# openSX70_MEROEC_V7-9C_20200625-TCS3200.net
KiCad netlist of a schematic drawn in EAGLE
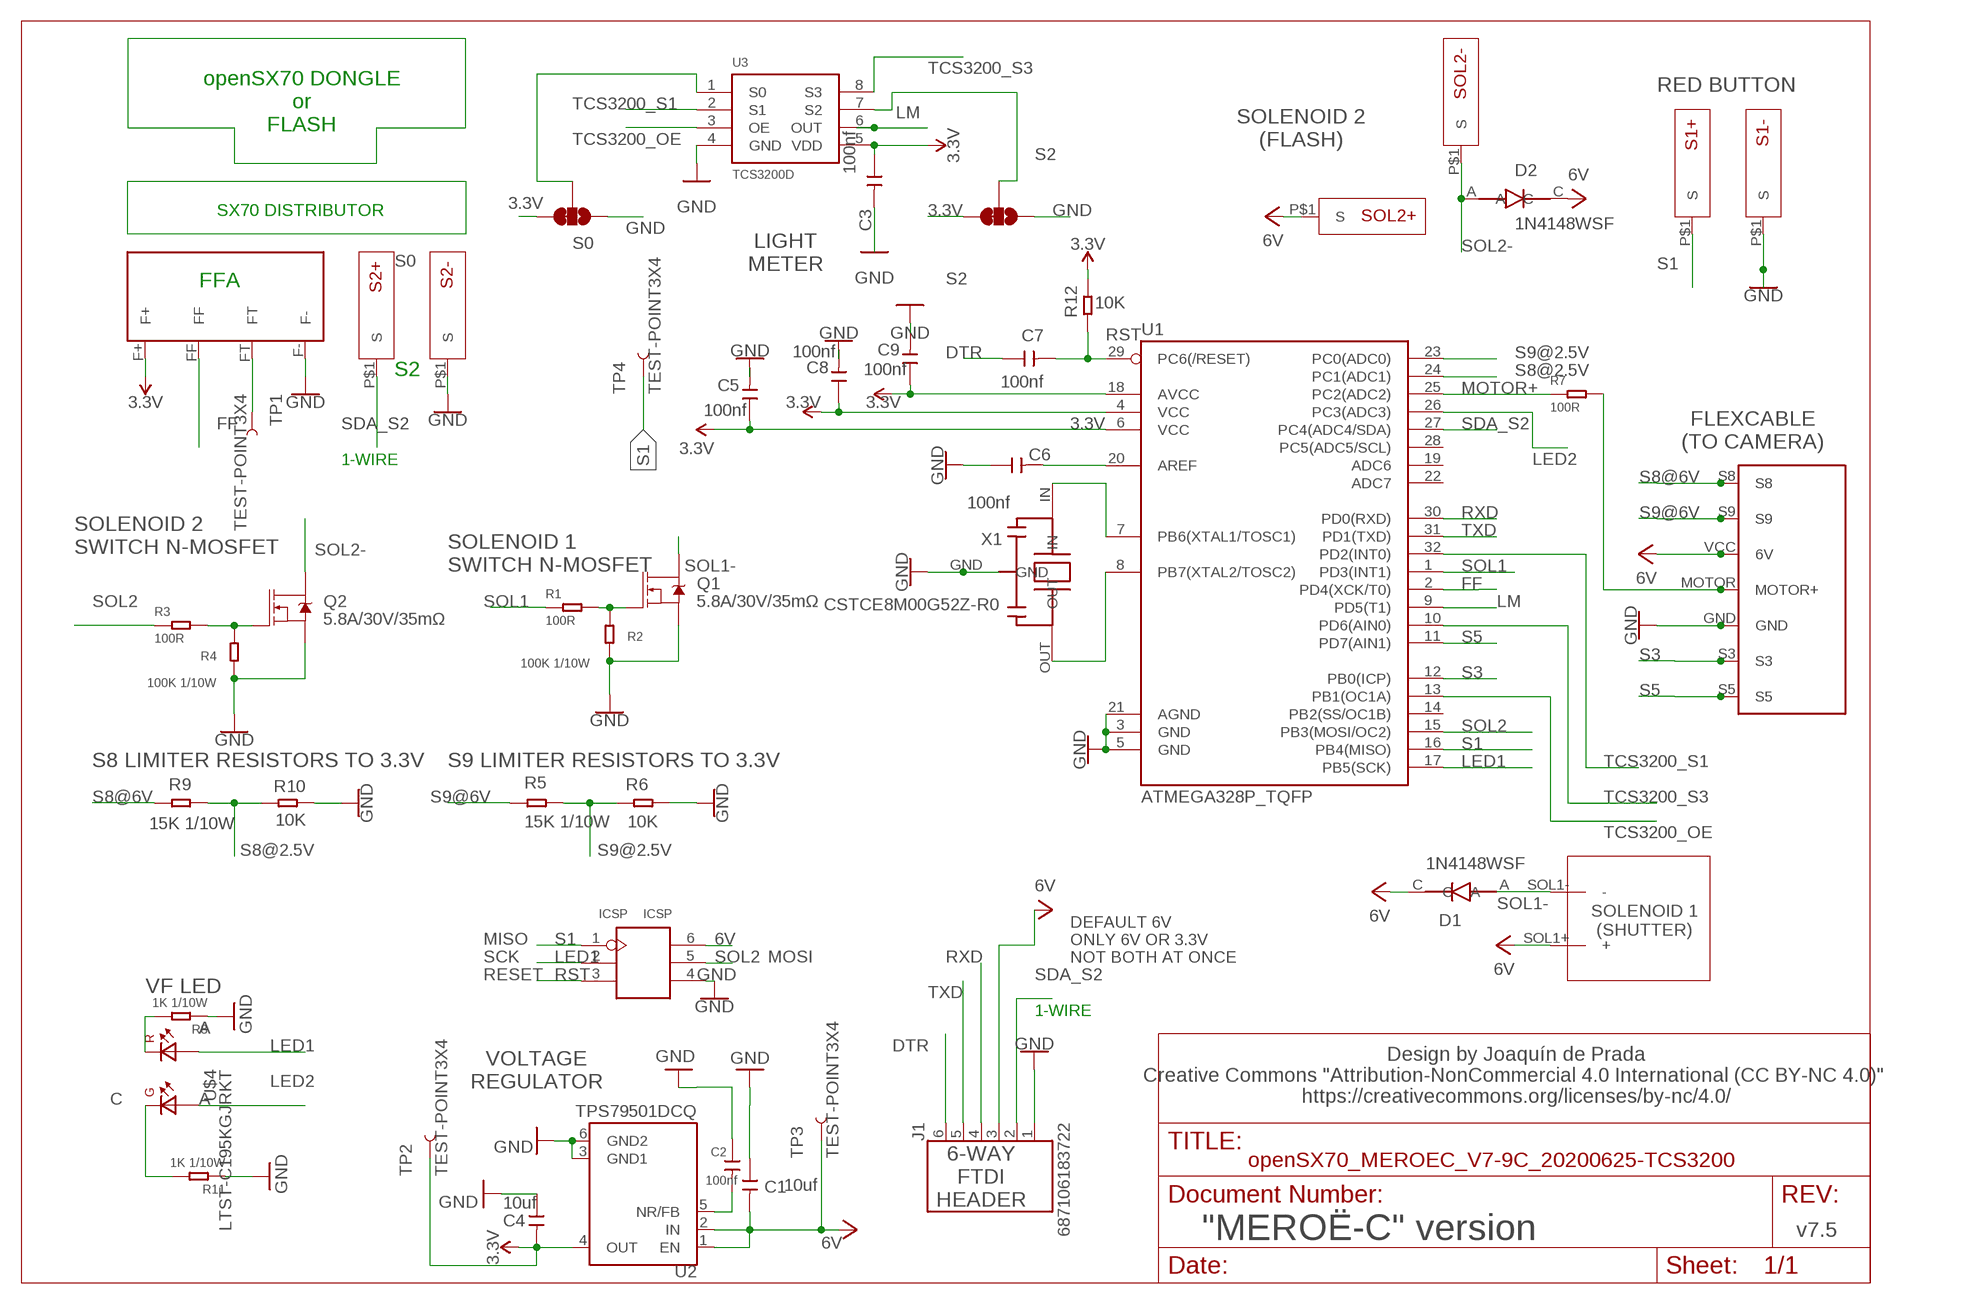
[diagram p0: schematic, sheet 1]

(export (version "E")
  (design (tool "Eeschema 10.0.6"))
  (components
    (comp (ref "C1")
      (value "10uf")
      (footprint "eagle-import:C0603")
      (fields (field (name "MPN") "CC0603KRX5R6BB106"))
      (libsource (lib "eagle-import") (part "CERAMIC-10UF-10V-10%-X5R(0603)"))
    )
    (comp (ref "C2")
      (value "100nf")
      (footprint "eagle-import:C0603")
      (fields (field (name "MPN") "CC0603KRX7R9BB104"))
      (libsource (lib "eagle-import") (part "CERAMIC-100NF-50V-10%-X7R(0603)"))
    )
    (comp (ref "C3")
      (value "100nf")
      (footprint "eagle-import:C0603")
      (fields (field (name "MPN") "CC0603KRX7R9BB104"))
      (libsource (lib "eagle-import") (part "CERAMIC-100NF-50V-10%-X7R(0603)"))
    )
    (comp (ref "C4")
      (value "10uf")
      (footprint "eagle-import:C0603")
      (fields (field (name "MPN") "CC0603KRX5R6BB106"))
      (libsource (lib "eagle-import") (part "CERAMIC-10UF-10V-10%-X5R(0603)"))
    )
    (comp (ref "C5")
      (value "100nf")
      (footprint "eagle-import:C0603")
      (fields (field (name "MPN") "CC0603KRX7R9BB104"))
      (libsource (lib "eagle-import") (part "CERAMIC-100NF-50V-10%-X7R(0603)"))
    )
    (comp (ref "C6")
      (value "100nf")
      (footprint "eagle-import:C0603")
      (fields (field (name "MPN") "CC0603KRX7R9BB104"))
      (libsource (lib "eagle-import") (part "CERAMIC-100NF-50V-10%-X7R(0603)"))
    )
    (comp (ref "C7")
      (value "100nf")
      (footprint "eagle-import:C0603")
      (fields (field (name "MPN") "CC0603KRX7R9BB104"))
      (libsource (lib "eagle-import") (part "CERAMIC-100NF-50V-10%-X7R(0603)"))
    )
    (comp (ref "C8")
      (value "100nf")
      (footprint "eagle-import:C0603")
      (fields (field (name "MPN") "CC0603KRX7R9BB104"))
      (libsource (lib "eagle-import") (part "CERAMIC-100NF-50V-10%-X7R(0603)"))
    )
    (comp (ref "C9")
      (value "100nf")
      (footprint "eagle-import:C0603")
      (fields (field (name "MPN") "CC0603KRX7R9BB104"))
      (libsource (lib "eagle-import") (part "CERAMIC-100NF-50V-10%-X7R(0603)"))
    )
    (comp (ref "D1")
      (value "1N4148WSF")
      (footprint "eagle-import:SODFL2512X100N")
      (fields (field (name "MANUFACTURER") "Fairchild Semiconductor"))
      (libsource (lib "eagle-import") (part "1N4148WS"))
    )
    (comp (ref "D2")
      (value "1N4148WSF")
      (footprint "eagle-import:SODFL2512X100N")
      (fields (field (name "MANUFACTURER") "Fairchild Semiconductor"))
      (libsource (lib "eagle-import") (part "1N4148WS"))
    )
    (comp (ref "ICSP")
      (value "ICSP")
      (footprint "eagle-import:H2X3-2.54")
      (libsource (lib "eagle-import") (part "ICSP"))
    )
    (comp (ref "J1")
      (value "687106183722")
      (footprint "eagle-import:687106183722")
      (fields (field (name "MF") "Wurth Electronics"))
      (libsource (lib "eagle-import") (part "687106183722"))
    )
    (comp (ref "Q1")
      (value "5.8A/30V/35mΩ")
      (footprint "eagle-import:SOT23-3")
      (libsource (lib "eagle-import") (part "MOSFET-NCH-AO3404A"))
    )
    (comp (ref "Q2")
      (value "5.8A/30V/35mΩ")
      (footprint "eagle-import:SOT23-3")
      (libsource (lib "eagle-import") (part "MOSFET-NCH-AO3404A"))
    )
    (comp (ref "R1")
      (value "100R")
      (footprint "eagle-import:R0603")
      (fields (field (name "MPN") "RC0603JR-07100RL"))
      (libsource (lib "eagle-import") (part "SMD-RES-100R-5%-1/10W(0603)"))
    )
    (comp (ref "R2")
      (value "100K 1/10W")
      (footprint "eagle-import:R0603")
      (fields (field (name "MPN") "RC0603JR-07100KL"))
      (libsource (lib "eagle-import") (part "SMD-RES-100K-5%-1/10W(0603)"))
    )
    (comp (ref "R3")
      (value "100R")
      (footprint "eagle-import:R0603")
      (fields (field (name "MPN") "RC0603JR-07100RL"))
      (libsource (lib "eagle-import") (part "SMD-RES-100R-5%-1/10W(0603)"))
    )
    (comp (ref "R4")
      (value "100K 1/10W")
      (footprint "eagle-import:R0603")
      (fields (field (name "MPN") "RC0603JR-07100KL"))
      (libsource (lib "eagle-import") (part "SMD-RES-100K-5%-1/10W(0603)"))
    )
    (comp (ref "R5")
      (value "15K 1/10W")
      (footprint "eagle-import:R0603")
      (fields (field (name "MPN") "RC0603FR-0715KL"))
      (libsource (lib "eagle-import") (part "SMD-RES-15K-1%-1/10W(0603)"))
    )
    (comp (ref "R6")
      (value "10K")
      (footprint "eagle-import:R0603")
      (fields (field (name "MPN") "RC0603FR-0710KL"))
      (libsource (lib "eagle-import") (part "SMD-RES-10K-1%-1/10W(0603)"))
    )
    (comp (ref "R7")
      (value "100R")
      (footprint "eagle-import:R0603")
      (fields (field (name "MPN") "RC0603JR-07100RL"))
      (libsource (lib "eagle-import") (part "SMD-RES-100R-5%-1/10W(0603)"))
    )
    (comp (ref "R8")
      (value "1K 1/10W")
      (footprint "eagle-import:R0603")
      (fields (field (name "MPN") "RC0603JR-071KL"))
      (libsource (lib "eagle-import") (part "SMD-RES-1K-5%-1/10W(0603)"))
    )
    (comp (ref "R9")
      (value "15K 1/10W")
      (footprint "eagle-import:R0603")
      (fields (field (name "MPN") "RC0603FR-0715KL"))
      (libsource (lib "eagle-import") (part "SMD-RES-15K-1%-1/10W(0603)"))
    )
    (comp (ref "R10")
      (value "10K")
      (footprint "eagle-import:R0603")
      (fields (field (name "MPN") "RC0603FR-0710KL"))
      (libsource (lib "eagle-import") (part "SMD-RES-10K-1%-1/10W(0603)"))
    )
    (comp (ref "R11")
      (value "1K 1/10W")
      (footprint "eagle-import:R0603")
      (fields (field (name "MPN") "RC0603JR-071KL"))
      (libsource (lib "eagle-import") (part "SMD-RES-1K-5%-1/10W(0603)"))
    )
    (comp (ref "R12")
      (value "10K")
      (footprint "eagle-import:R0603")
      (fields (field (name "MPN") "RC0603FR-0710KL"))
      (libsource (lib "eagle-import") (part "SMD-RES-10K-1%-1/10W(0603)"))
    )
    (comp (ref "S0")
      (value "S0")
      (footprint "eagle-import:SMT-JUMPER_3_1-NC_TRACE_SILK")
      (libsource (lib "eagle-import") (part "JUMPER-SMT_3_1-NC_TRACE_SILK"))
    )
    (comp (ref "S1+")
      (value "SX70-S-PAD-NEW")
      (footprint "eagle-import:SX70-S-PAD2")
      (libsource (lib "eagle-import") (part "SX70-S-PAD-NEW"))
    )
    (comp (ref "S1-")
      (value "SX70-S-PAD-NEW")
      (footprint "eagle-import:SX70-S-PAD2")
      (libsource (lib "eagle-import") (part "SX70-S-PAD-NEW"))
    )
    (comp (ref "S2")
      (value "S2")
      (footprint "eagle-import:SMT-JUMPER_3_1-NC_TRACE_SILK")
      (libsource (lib "eagle-import") (part "JUMPER-SMT_3_1-NC_TRACE_SILK"))
    )
    (comp (ref "S2+")
      (value "SX70-S-PAD-NEW")
      (footprint "eagle-import:SX70-S-PAD2")
      (libsource (lib "eagle-import") (part "SX70-S-PAD-NEW"))
    )
    (comp (ref "S2-")
      (value "SX70-S-PAD-NEW")
      (footprint "eagle-import:SX70-S-PAD2")
      (libsource (lib "eagle-import") (part "SX70-S-PAD-NEW"))
    )
    (comp (ref "SOL1")
      (value "SX70-SOLENOID1-2PADS")
      (footprint "eagle-import:SX70-SOLENOID1-2")
      (libsource (lib "eagle-import") (part "SX70-SOLENOID1-2PADS"))
    )
    (comp (ref "SOL2+")
      (value "SX70-S-PAD-NEW")
      (footprint "eagle-import:SX70-S-PAD2")
      (libsource (lib "eagle-import") (part "SX70-S-PAD-NEW"))
    )
    (comp (ref "SOL2-")
      (value "SX70-S-PAD-NEW")
      (footprint "eagle-import:SX70-S-PAD2")
      (libsource (lib "eagle-import") (part "SX70-S-PAD-NEW"))
    )
    (comp (ref "TP1")
      (value "TEST-POINT3X4")
      (footprint "eagle-import:PAD.03X.04")
      (libsource (lib "eagle-import") (part "TEST-POINT3X4"))
    )
    (comp (ref "TP2")
      (value "TEST-POINT3X4")
      (footprint "eagle-import:PAD.03X.04")
      (libsource (lib "eagle-import") (part "TEST-POINT3X4"))
    )
    (comp (ref "TP3")
      (value "TEST-POINT3X4")
      (footprint "eagle-import:PAD.03X.04")
      (libsource (lib "eagle-import") (part "TEST-POINT3X4"))
    )
    (comp (ref "TP4")
      (value "TEST-POINT3X4")
      (footprint "eagle-import:PAD.03X.04")
      (libsource (lib "eagle-import") (part "TEST-POINT3X4"))
    )
    (comp (ref "U$1")
      (value "SX70-7-PAD")
      (footprint "eagle-import:SX70-7-PAD-PROPER")
      (libsource (lib "eagle-import") (part "SX70-7-PAD"))
    )
    (comp (ref "U$2")
      (value "FFA")
      (footprint "eagle-import:FFA-PAD-PACKAGE")
      (libsource (lib "eagle-import") (part "SX70-FFA-PAD"))
    )
    (comp (ref "U$4")
      (value "LTST-C195KGJRKT")
      (footprint "eagle-import:LTST-BILED-15X16")
      (fields (field (name "MF") "Lite-On Inc."))
      (libsource (lib "eagle-import") (part "LTST-C195KGJRKT"))
    )
    (comp (ref "U1")
      (value "ATMEGA328P_TQFP")
      (footprint "eagle-import:TQFP32-08")
      (libsource (lib "eagle-import") (part "ATMEGA328P_TQFP"))
    )
    (comp (ref "U2")
      (value "TPS79501DCQ")
      (footprint "eagle-import:SOT127P706X180-6N")
      (fields (field (name "MF") "Texas Instruments"))
      (libsource (lib "eagle-import") (part "TPS79501DCQ"))
    )
    (comp (ref "U3")
      (value "TCS3200D")
      (footprint "eagle-import:SOIC8")
      (fields (field (name "MF") "ams") (field (name "MP") "TCS3200D-TR"))
      (libsource (lib "eagle-import") (part "TCS3200D"))
    )
    (comp (ref "X1")
      (value "CSTCE8M00G52Z-R0")
      (footprint "eagle-import:CFP95P160X100-3N")
      (fields (field (name "MF") "Murata") (field (name "MP") "CSTCE16M0V53-R0"))
      (libsource (lib "eagle-import") (part "CSTCE16M0V53-R0"))
    )
  )
  (nets
    (net (code "1") (name "/DTR") (class "Default")
      (node (ref "C7") (pin "1") (pinfunction "1_1") (pintype "passive"))
      (node (ref "J1") (pin "6") (pinfunction "1_6") (pintype "passive"))
    )
    (net (code "2") (name "/FF") (class "Default")
      (node (ref "U$2") (pin "FF") (pinfunction "FF_FF") (pintype "bidirectional"))
      (node (ref "U1") (pin "2") (pinfunction "PD4(XCK/T0)_2") (pintype "bidirectional"))
    )
    (net (code "3") (name "/LED1") (class "Default")
      (node (ref "ICSP") (pin "2") (pinfunction "SCK_2") (pintype "bidirectional"))
      (node (ref "U$4") (pin "P$2") (pinfunction "A2_P$2") (pintype "passive"))
      (node (ref "U1") (pin "17") (pinfunction "PB5(SCK)_17") (pintype "bidirectional"))
    )
    (net (code "4") (name "/LED2") (class "Default")
      (node (ref "U$4") (pin "P$1") (pinfunction "A1_P$1") (pintype "passive"))
      (node (ref "U1") (pin "26") (pinfunction "PC3(ADC3)_26") (pintype "bidirectional"))
    )
    (net (code "5") (name "/LM") (class "Default")
      (node (ref "U1") (pin "9") (pinfunction "PD5(T1)_9") (pintype "bidirectional"))
      (node (ref "U3") (pin "6") (pinfunction "OUT_6") (pintype "bidirectional"))
    )
    (net (code "6") (name "/MOTOR+") (class "Default")
      (node (ref "R7") (pin "1") (pinfunction "1_1") (pintype "passive"))
      (node (ref "U1") (pin "25") (pinfunction "PC2(ADC2)_25") (pintype "bidirectional"))
    )
    (net (code "7") (name "/RST") (class "Default")
      (node (ref "C7") (pin "2") (pinfunction "2_2") (pintype "passive"))
      (node (ref "ICSP") (pin "3") (pinfunction "RST_3") (pintype "bidirectional"))
      (node (ref "R12") (pin "1") (pinfunction "1_1") (pintype "passive"))
      (node (ref "U1") (pin "29") (pinfunction "PC6(/RESET)_29") (pintype "bidirectional"))
    )
    (net (code "8") (name "/RXD") (class "Default")
      (node (ref "J1") (pin "4") (pinfunction "3_4") (pintype "passive"))
      (node (ref "U1") (pin "30") (pinfunction "PD0(RXD)_30") (pintype "bidirectional"))
    )
    (net (code "9") (name "/S3") (class "Default")
      (node (ref "U$1") (pin "S3") (pinfunction "S3_S3") (pintype "bidirectional"))
      (node (ref "U1") (pin "12") (pinfunction "PB0(ICP)_12") (pintype "bidirectional"))
    )
    (net (code "10") (name "/S5") (class "Default")
      (node (ref "U$1") (pin "S5") (pinfunction "S5_S5") (pintype "bidirectional"))
      (node (ref "U1") (pin "11") (pinfunction "PD7(AIN1)_11") (pintype "bidirectional"))
    )
    (net (code "11") (name "/S8@2.5V") (class "Default")
      (node (ref "R10") (pin "1") (pinfunction "1_1") (pintype "passive"))
      (node (ref "R9") (pin "2") (pinfunction "2_2") (pintype "passive"))
      (node (ref "U1") (pin "24") (pinfunction "PC1(ADC1)_24") (pintype "bidirectional"))
    )
    (net (code "12") (name "/S8@6V") (class "Default")
      (node (ref "R9") (pin "1") (pinfunction "1_1") (pintype "passive"))
      (node (ref "U$1") (pin "S8") (pinfunction "S8_S8") (pintype "bidirectional"))
    )
    (net (code "13") (name "/S9@2.5V") (class "Default")
      (node (ref "R5") (pin "2") (pinfunction "2_2") (pintype "passive"))
      (node (ref "R6") (pin "1") (pinfunction "1_1") (pintype "passive"))
      (node (ref "U1") (pin "23") (pinfunction "PC0(ADC0)_23") (pintype "bidirectional"))
    )
    (net (code "14") (name "/S9@6V") (class "Default")
      (node (ref "R5") (pin "1") (pinfunction "1_1") (pintype "passive"))
      (node (ref "U$1") (pin "S9") (pinfunction "S9_S9") (pintype "bidirectional"))
    )
    (net (code "15") (name "/SDA_S2") (class "Default")
      (node (ref "J1") (pin "2") (pinfunction "5_2") (pintype "passive"))
      (node (ref "S2+") (pin "P$1") (pinfunction "S_P$1") (pintype "bidirectional"))
      (node (ref "U1") (pin "27") (pinfunction "PC4(ADC4/SDA)_27") (pintype "bidirectional"))
    )
    (net (code "16") (name "/SOL1") (class "Default")
      (node (ref "R1") (pin "1") (pinfunction "1_1") (pintype "passive"))
      (node (ref "U1") (pin "1") (pinfunction "PD3(INT1)_1") (pintype "bidirectional"))
    )
    (net (code "17") (name "/SOL1-") (class "Default")
      (node (ref "D1") (pin "A") (pinfunction "A_A") (pintype "passive"))
      (node (ref "Q1") (pin "3") (pinfunction "D_3") (pintype "bidirectional"))
      (node (ref "SOL1") (pin "SOL1-") (pinfunction "-_SOL1-") (pintype "bidirectional"))
    )
    (net (code "18") (name "/SOL2") (class "Default")
      (node (ref "ICSP") (pin "5") (pinfunction "MOSI_5") (pintype "bidirectional"))
      (node (ref "R3") (pin "1") (pinfunction "1_1") (pintype "passive"))
      (node (ref "U1") (pin "15") (pinfunction "PB3(MOSI/OC2)_15") (pintype "bidirectional"))
    )
    (net (code "19") (name "/SOL2-") (class "Default")
      (node (ref "D2") (pin "A") (pinfunction "A_A") (pintype "passive"))
      (node (ref "Q2") (pin "3") (pinfunction "D_3") (pintype "bidirectional"))
      (node (ref "SOL2-") (pin "P$1") (pinfunction "S_P$1") (pintype "bidirectional"))
    )
    (net (code "20") (name "/TCS3200_OE") (class "Default")
      (node (ref "U1") (pin "13") (pinfunction "PB1(OC1A)_13") (pintype "bidirectional"))
      (node (ref "U3") (pin "3") (pinfunction "OE_3") (pintype "bidirectional"))
    )
    (net (code "21") (name "/TCS3200_S1") (class "Default")
      (node (ref "U1") (pin "32") (pinfunction "PD2(INT0)_32") (pintype "bidirectional"))
      (node (ref "U3") (pin "2") (pinfunction "S1_2") (pintype "bidirectional"))
    )
    (net (code "22") (name "/TCS3200_S3") (class "Default")
      (node (ref "U1") (pin "10") (pinfunction "PD6(AIN0)_10") (pintype "bidirectional"))
      (node (ref "U3") (pin "8") (pinfunction "S3_8") (pintype "bidirectional"))
    )
    (net (code "23") (name "/TXD") (class "Default")
      (node (ref "J1") (pin "5") (pinfunction "2_5") (pintype "passive"))
      (node (ref "U1") (pin "31") (pinfunction "PD1(TXD)_31") (pintype "bidirectional"))
    )
    (net (code "24") (name "3.3V") (class "Default")
      (node (ref "C3") (pin "1") (pinfunction "1_1") (pintype "passive"))
      (node (ref "C4") (pin "2") (pinfunction "2_2") (pintype "passive"))
      (node (ref "C5") (pin "1") (pinfunction "1_1") (pintype "passive"))
      (node (ref "C8") (pin "1") (pinfunction "1_1") (pintype "passive"))
      (node (ref "C9") (pin "1") (pinfunction "1_1") (pintype "passive"))
      (node (ref "R12") (pin "2") (pinfunction "2_2") (pintype "passive"))
      (node (ref "S0") (pin "3") (pinfunction "3_3") (pintype "passive"))
      (node (ref "S2") (pin "3") (pinfunction "3_3") (pintype "passive"))
      (node (ref "TP2") (pin "P$1") (pinfunction "1_P$1") (pintype "bidirectional"))
      (node (ref "U$2") (pin "F+") (pinfunction "F+_F+") (pintype "bidirectional"))
      (node (ref "U1") (pin "18") (pinfunction "AVCC_18") (pintype "bidirectional"))
      (node (ref "U1") (pin "4") (pinfunction "VCC_4") (pintype "bidirectional"))
      (node (ref "U1") (pin "6") (pinfunction "VCC_6") (pintype "bidirectional"))
      (node (ref "U2") (pin "4") (pinfunction "OUT_4") (pintype "output"))
      (node (ref "U3") (pin "5") (pinfunction "VDD_5") (pintype "bidirectional"))
    )
    (net (code "25") (name "6V") (class "Default")
      (node (ref "C1") (pin "2") (pinfunction "2_2") (pintype "passive"))
      (node (ref "D1") (pin "C") (pinfunction "C_C") (pintype "passive"))
      (node (ref "D2") (pin "C") (pinfunction "C_C") (pintype "passive"))
      (node (ref "ICSP") (pin "6") (pinfunction "VCC_6") (pintype "bidirectional"))
      (node (ref "J1") (pin "3") (pinfunction "4_3") (pintype "passive"))
      (node (ref "SOL1") (pin "SOL1+") (pinfunction "+_SOL1+") (pintype "bidirectional"))
      (node (ref "SOL2+") (pin "P$1") (pinfunction "S_P$1") (pintype "bidirectional"))
      (node (ref "TP3") (pin "P$1") (pinfunction "1_P$1") (pintype "bidirectional"))
      (node (ref "U$1") (pin "VCC") (pinfunction "6V_VCC") (pintype "bidirectional"))
      (node (ref "U2") (pin "1") (pinfunction "EN_1") (pintype "input"))
      (node (ref "U2") (pin "2") (pinfunction "IN_2") (pintype "input"))
    )
    (net (code "26") (name "GND") (class "Default")
      (node (ref "C1") (pin "1") (pinfunction "1_1") (pintype "passive"))
      (node (ref "C2") (pin "1") (pinfunction "1_1") (pintype "passive"))
      (node (ref "C3") (pin "2") (pinfunction "2_2") (pintype "passive"))
      (node (ref "C4") (pin "1") (pinfunction "1_1") (pintype "passive"))
      (node (ref "C5") (pin "2") (pinfunction "2_2") (pintype "passive"))
      (node (ref "C6") (pin "1") (pinfunction "1_1") (pintype "passive"))
      (node (ref "C8") (pin "2") (pinfunction "2_2") (pintype "passive"))
      (node (ref "C9") (pin "2") (pinfunction "2_2") (pintype "passive"))
      (node (ref "ICSP") (pin "4") (pinfunction "GND_4") (pintype "bidirectional"))
      (node (ref "J1") (pin "1") (pinfunction "6_1") (pintype "passive"))
      (node (ref "Q1") (pin "2") (pinfunction "S_2") (pintype "bidirectional"))
      (node (ref "Q2") (pin "2") (pinfunction "S_2") (pintype "bidirectional"))
      (node (ref "R10") (pin "2") (pinfunction "2_2") (pintype "passive"))
      (node (ref "R11") (pin "1") (pinfunction "1_1") (pintype "passive"))
      (node (ref "R2") (pin "1") (pinfunction "1_1") (pintype "passive"))
      (node (ref "R4") (pin "1") (pinfunction "1_1") (pintype "passive"))
      (node (ref "R6") (pin "2") (pinfunction "2_2") (pintype "passive"))
      (node (ref "R8") (pin "1") (pinfunction "1_1") (pintype "passive"))
      (node (ref "S0") (pin "1") (pinfunction "1_1") (pintype "passive"))
      (node (ref "S1-") (pin "P$1") (pinfunction "S_P$1") (pintype "bidirectional"))
      (node (ref "S2") (pin "1") (pinfunction "1_1") (pintype "passive"))
      (node (ref "S2-") (pin "P$1") (pinfunction "S_P$1") (pintype "bidirectional"))
      (node (ref "U$1") (pin "GND") (pinfunction "GND_GND") (pintype "bidirectional"))
      (node (ref "U$2") (pin "F-") (pinfunction "F-_F-") (pintype "bidirectional"))
      (node (ref "U1") (pin "21") (pinfunction "AGND_21") (pintype "bidirectional"))
      (node (ref "U1") (pin "3") (pinfunction "GND_3") (pintype "bidirectional"))
      (node (ref "U1") (pin "5") (pinfunction "GND_5") (pintype "bidirectional"))
      (node (ref "U2") (pin "3") (pinfunction "GND1_3") (pintype "power_in"))
      (node (ref "U2") (pin "6") (pinfunction "GND2_6") (pintype "power_in"))
      (node (ref "U3") (pin "4") (pinfunction "GND_4") (pintype "bidirectional"))
      (node (ref "X1") (pin "GND") (pinfunction "GND_GND") (pintype "passive"))
    )
    (net (code "27") (name "Net-(Q1-G)") (class "Default")
      (node (ref "Q1") (pin "1") (pinfunction "G_1") (pintype "bidirectional"))
      (node (ref "R1") (pin "2") (pinfunction "2_2") (pintype "passive"))
      (node (ref "R2") (pin "2") (pinfunction "2_2") (pintype "passive"))
    )
    (net (code "28") (name "Net-(Q2-G)") (class "Default")
      (node (ref "Q2") (pin "1") (pinfunction "G_1") (pintype "bidirectional"))
      (node (ref "R3") (pin "2") (pinfunction "2_2") (pintype "passive"))
      (node (ref "R4") (pin "2") (pinfunction "2_2") (pintype "passive"))
    )
    (net (code "29") (name "Net-(TP1-1)") (class "Default")
      (node (ref "TP1") (pin "P$1") (pinfunction "1_P$1") (pintype "bidirectional"))
      (node (ref "U$2") (pin "FT") (pinfunction "FT_FT") (pintype "bidirectional"))
    )
    (net (code "30") (name "Net-(U$1-MOTOR+)") (class "Default")
      (node (ref "R7") (pin "2") (pinfunction "2_2") (pintype "passive"))
      (node (ref "U$1") (pin "MOTOR") (pinfunction "MOTOR+_MOTOR") (pintype "bidirectional"))
    )
    (net (code "31") (name "Net-(U$4-K1)") (class "Default")
      (node (ref "R11") (pin "2") (pinfunction "2_2") (pintype "passive"))
      (node (ref "U$4") (pin "P$3") (pinfunction "K1_P$3") (pintype "passive"))
    )
    (net (code "32") (name "Net-(U$4-K2)") (class "Default")
      (node (ref "R8") (pin "2") (pinfunction "2_2") (pintype "passive"))
      (node (ref "U$4") (pin "P$4") (pinfunction "K2_P$4") (pintype "passive"))
    )
    (net (code "33") (name "Net-(U1-AREF)") (class "Default")
      (node (ref "C6") (pin "2") (pinfunction "2_2") (pintype "passive"))
      (node (ref "U1") (pin "20") (pinfunction "AREF_20") (pintype "bidirectional"))
    )
    (net (code "34") (name "Net-(U1-PB6(XTAL1{slash}TOSC1))") (class "Default")
      (node (ref "U1") (pin "7") (pinfunction "PB6(XTAL1/TOSC1)_7") (pintype "bidirectional"))
      (node (ref "X1") (pin "IN") (pinfunction "IN_IN") (pintype "input"))
    )
    (net (code "35") (name "Net-(U1-PB7(XTAL2{slash}TOSC2))") (class "Default")
      (node (ref "U1") (pin "8") (pinfunction "PB7(XTAL2/TOSC2)_8") (pintype "bidirectional"))
      (node (ref "X1") (pin "OUT") (pinfunction "OUT_OUT") (pintype "output"))
    )
    (net (code "36") (name "Net-(U2-NR{slash}FB)") (class "Default")
      (node (ref "C2") (pin "2") (pinfunction "2_2") (pintype "passive"))
      (node (ref "U2") (pin "5") (pinfunction "NR/FB_5") (pintype "input"))
    )
    (net (code "37") (name "Net-(U3-S0)") (class "Default")
      (node (ref "S0") (pin "2") (pinfunction "2_2") (pintype "passive"))
      (node (ref "U3") (pin "1") (pinfunction "S0_1") (pintype "bidirectional"))
    )
    (net (code "38") (name "Net-(U3-S2)") (class "Default")
      (node (ref "S2") (pin "2") (pinfunction "2_2") (pintype "passive"))
      (node (ref "U3") (pin "7") (pinfunction "S2_7") (pintype "bidirectional"))
    )
    (net (code "39") (name "S1") (class "Default")
      (node (ref "ICSP") (pin "1") (pinfunction "MISO_1") (pintype "bidirectional"))
      (node (ref "S1+") (pin "P$1") (pinfunction "S_P$1") (pintype "bidirectional"))
      (node (ref "TP4") (pin "P$1") (pinfunction "1_P$1") (pintype "bidirectional"))
      (node (ref "U1") (pin "16") (pinfunction "PB4(MISO)_16") (pintype "bidirectional"))
    )
    (net (code "40") (name "unconnected-(U1-ADC6-Pad19)") (class "Default")
      (node (ref "U1") (pin "19") (pinfunction "ADC6_19") (pintype "bidirectional"))
    )
    (net (code "41") (name "unconnected-(U1-ADC7-Pad22)") (class "Default")
      (node (ref "U1") (pin "22") (pinfunction "ADC7_22") (pintype "bidirectional"))
    )
    (net (code "42") (name "unconnected-(U1-PB2(SS{slash}OC1B)-Pad14)") (class "Default")
      (node (ref "U1") (pin "14") (pinfunction "PB2(SS/OC1B)_14") (pintype "bidirectional"))
    )
    (net (code "43") (name "unconnected-(U1-PC5(ADC5{slash}SCL)-Pad28)") (class "Default")
      (node (ref "U1") (pin "28") (pinfunction "PC5(ADC5/SCL)_28") (pintype "bidirectional"))
    )
  )
)
